# basic_board.net
KiCad netlist of a schematic drawn in EAGLE
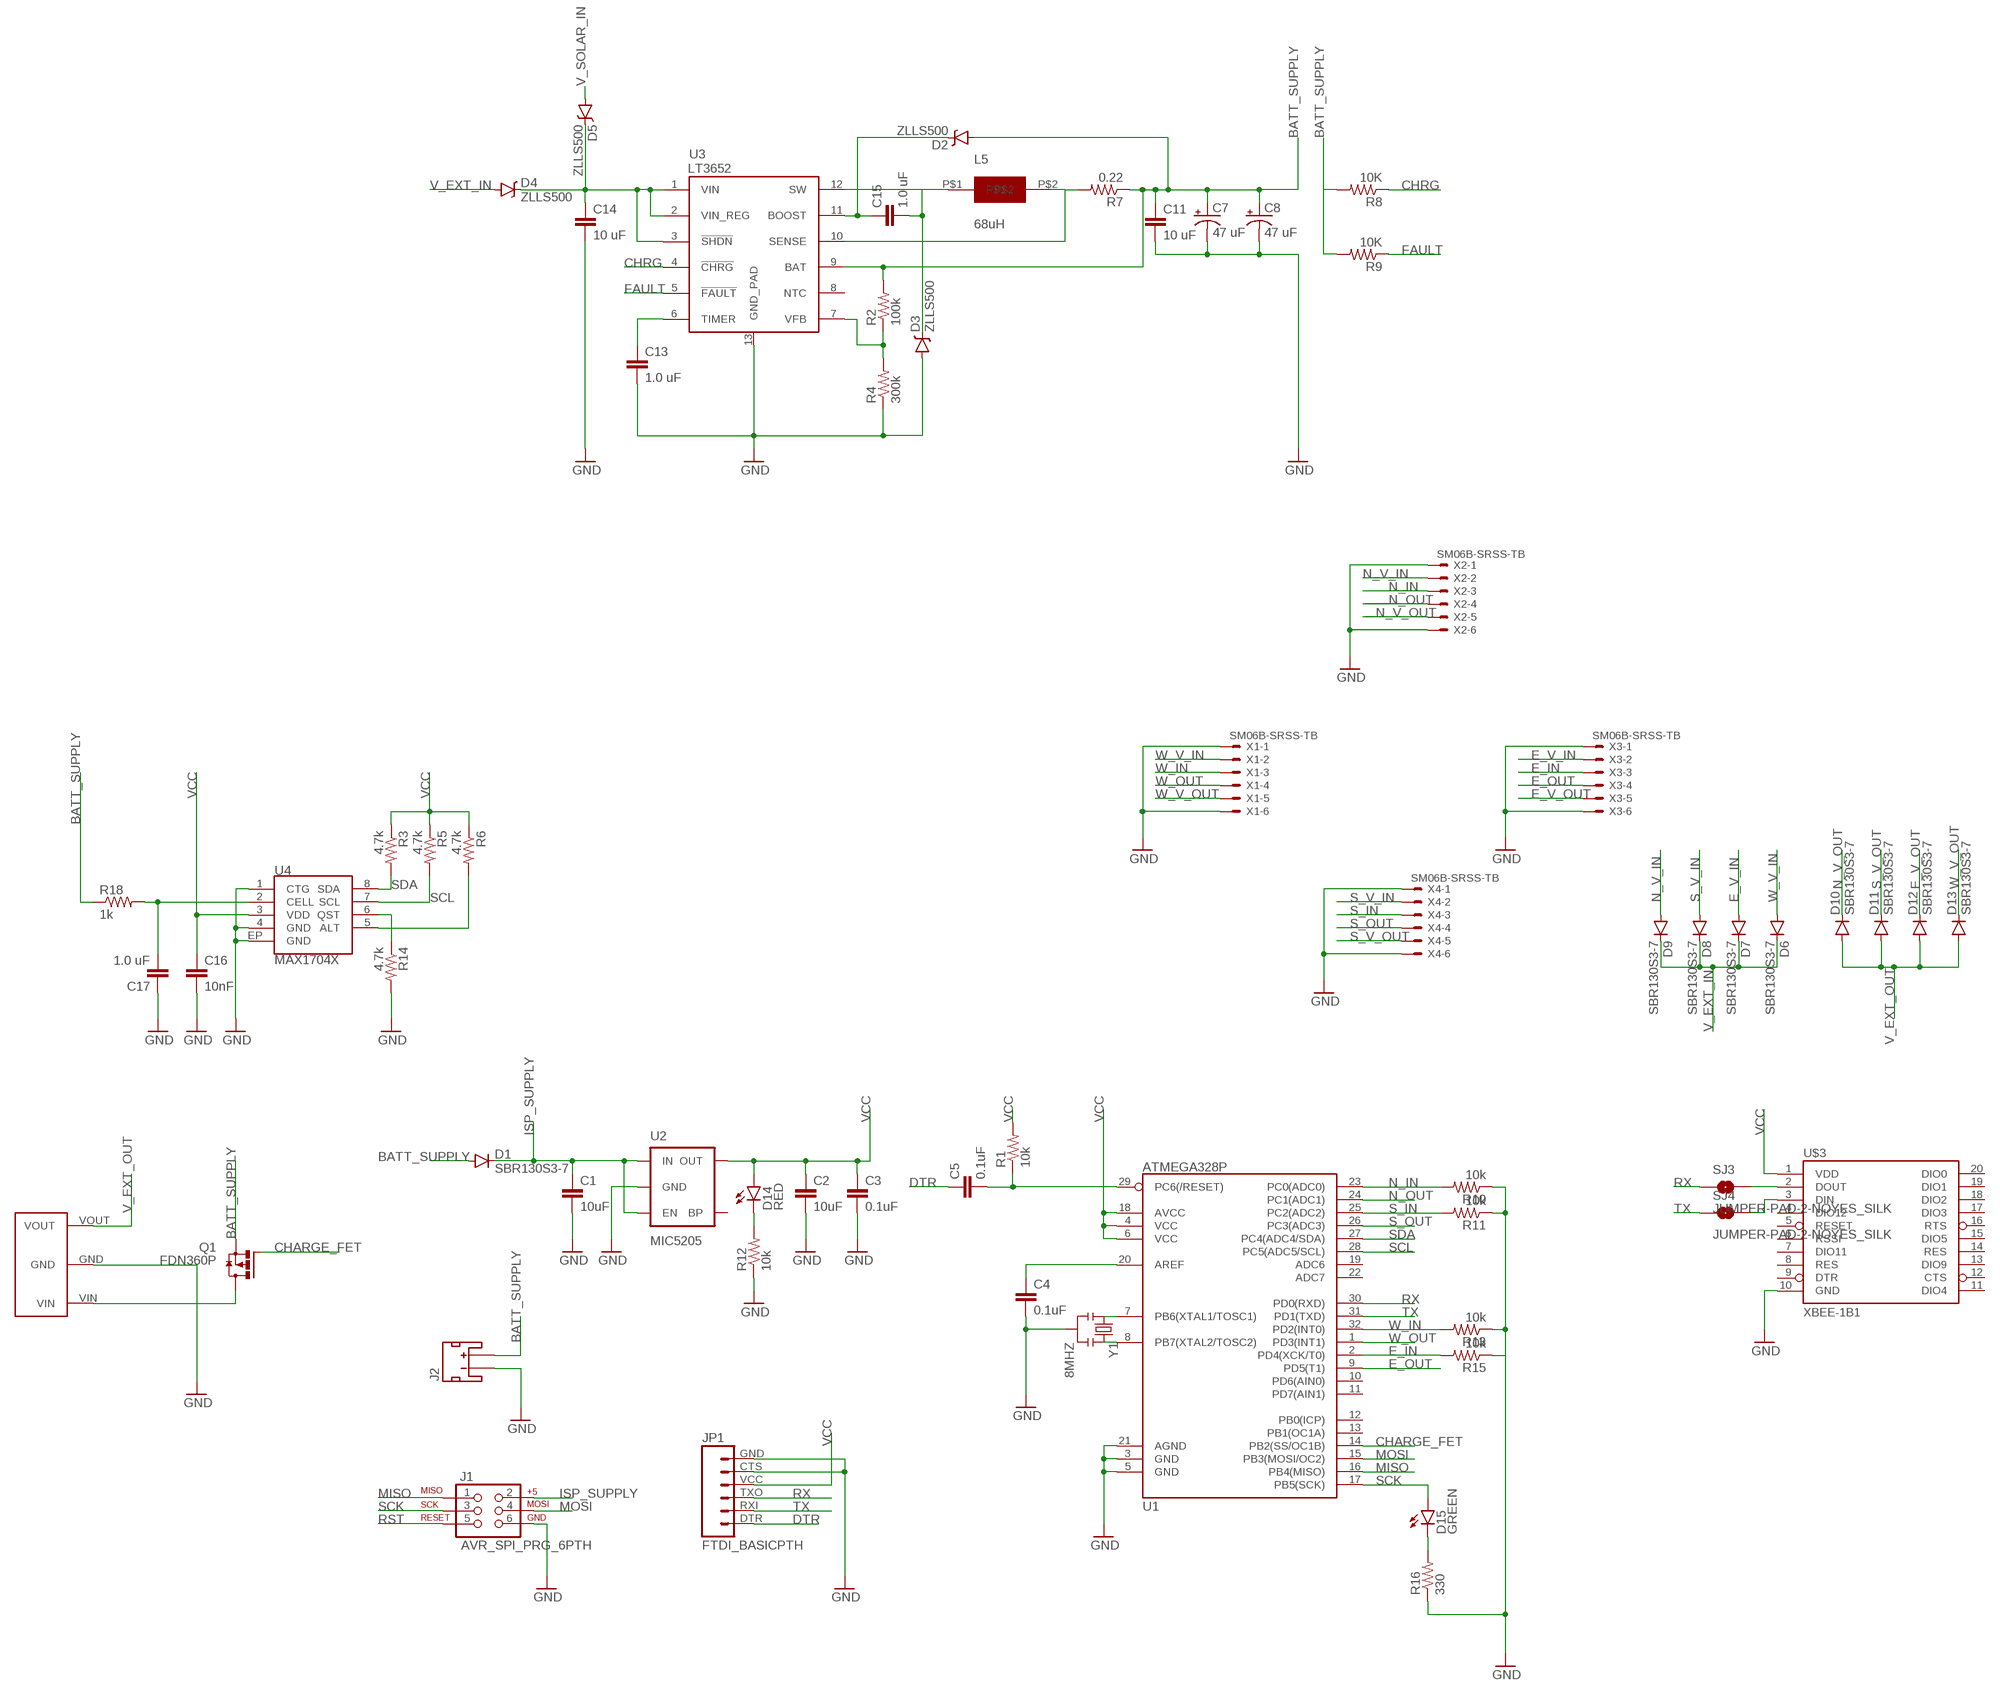
[diagram p0: schematic, sheet 1]

(export (version "E")
  (design (tool "Eeschema 10.0.6"))
  (components
    (comp (ref "C1")
      (value "10uF")
      (footprint "eagle-import:1206")
      (libsource (lib "eagle-import") (part "CAP1206"))
    )
    (comp (ref "C2")
      (value "10uF")
      (footprint "eagle-import:1206")
      (libsource (lib "eagle-import") (part "CAP1206"))
    )
    (comp (ref "C3")
      (value "0.1uF")
      (footprint "eagle-import:1206")
      (libsource (lib "eagle-import") (part "CAP1206"))
    )
    (comp (ref "C4")
      (value "0.1uF")
      (footprint "eagle-import:0603-CAP")
      (libsource (lib "eagle-import") (part "SparkFun-Passives_CAP0603-CAP"))
    )
    (comp (ref "C5")
      (value "0.1uF")
      (footprint "eagle-import:0603-CAP")
      (libsource (lib "eagle-import") (part "SparkFun-Passives_CAP0603-CAP"))
    )
    (comp (ref "C7")
      (value "47 uF")
      (footprint "eagle-import:EIA3216")
      (libsource (lib "eagle-import") (part "CAP_POL1206"))
    )
    (comp (ref "C8")
      (value "47 uF")
      (footprint "eagle-import:EIA3216")
      (libsource (lib "eagle-import") (part "CAP_POL1206"))
    )
    (comp (ref "C11")
      (value "10 uF")
      (footprint "eagle-import:1206")
      (libsource (lib "eagle-import") (part "10UF-6.3V-20%(1206)"))
    )
    (comp (ref "C13")
      (value "1.0 uF")
      (footprint "eagle-import:1206")
      (libsource (lib "eagle-import") (part "10UF-6.3V-20%(1206)"))
    )
    (comp (ref "C14")
      (value "10 uF")
      (footprint "eagle-import:1206")
      (libsource (lib "eagle-import") (part "10UF-6.3V-20%(1206)"))
    )
    (comp (ref "C15")
      (value "1.0 uF")
      (footprint "eagle-import:1206")
      (libsource (lib "eagle-import") (part "10UF-6.3V-20%(1206)"))
    )
    (comp (ref "C16")
      (value "10nF")
      (footprint "eagle-import:0603-CAP")
      (libsource (lib "eagle-import") (part "SparkFun-Passives_CAP0603-CAP"))
    )
    (comp (ref "C17")
      (value "1.0 uF")
      (footprint "eagle-import:0603-CAP")
      (libsource (lib "eagle-import") (part "SparkFun-Passives_CAP0603-CAP"))
    )
    (comp (ref "D1")
      (value "SBR130S3-7")
      (footprint "eagle-import:SOD-323")
      (libsource (lib "eagle-import") (part "DIODESOD"))
    )
    (comp (ref "D2")
      (value "ZLLS500")
      (footprint "eagle-import:SOT23")
      (libsource (lib "eagle-import") (part "ZLLS500ZLLS500"))
    )
    (comp (ref "D3")
      (value "ZLLS500")
      (footprint "eagle-import:SOT23")
      (libsource (lib "eagle-import") (part "ZLLS500ZLLS500"))
    )
    (comp (ref "D4")
      (value "ZLLS500")
      (footprint "eagle-import:SOT23")
      (libsource (lib "eagle-import") (part "ZLLS500ZLLS500"))
    )
    (comp (ref "D5")
      (value "ZLLS500")
      (footprint "eagle-import:SOT23")
      (libsource (lib "eagle-import") (part "ZLLS500ZLLS500"))
    )
    (comp (ref "D6")
      (value "SBR130S3-7")
      (footprint "eagle-import:SOD-323")
      (libsource (lib "eagle-import") (part "DIODESOD"))
    )
    (comp (ref "D7")
      (value "SBR130S3-7")
      (footprint "eagle-import:SOD-323")
      (libsource (lib "eagle-import") (part "DIODESOD"))
    )
    (comp (ref "D8")
      (value "SBR130S3-7")
      (footprint "eagle-import:SOD-323")
      (libsource (lib "eagle-import") (part "DIODESOD"))
    )
    (comp (ref "D9")
      (value "SBR130S3-7")
      (footprint "eagle-import:SOD-323")
      (libsource (lib "eagle-import") (part "DIODESOD"))
    )
    (comp (ref "D10")
      (value "SBR130S3-7")
      (footprint "eagle-import:SOD-323")
      (libsource (lib "eagle-import") (part "DIODESOD"))
    )
    (comp (ref "D11")
      (value "SBR130S3-7")
      (footprint "eagle-import:SOD-323")
      (libsource (lib "eagle-import") (part "DIODESOD"))
    )
    (comp (ref "D12")
      (value "SBR130S3-7")
      (footprint "eagle-import:SOD-323")
      (libsource (lib "eagle-import") (part "DIODESOD"))
    )
    (comp (ref "D13")
      (value "SBR130S3-7")
      (footprint "eagle-import:SOD-323")
      (libsource (lib "eagle-import") (part "DIODESOD"))
    )
    (comp (ref "D14")
      (value "RED")
      (footprint "eagle-import:LED-0603")
      (libsource (lib "eagle-import") (part "LED-RED0603"))
    )
    (comp (ref "D15")
      (value "GREEN")
      (footprint "eagle-import:LED-0603")
      (libsource (lib "eagle-import") (part "LED-GREEN0603"))
    )
    (comp (ref "J1")
      (value "AVR_SPI_PRG_6PTH")
      (footprint "eagle-import:2X3")
      (libsource (lib "eagle-import") (part "AVR_SPI_PRG_6PTH"))
    )
    (comp (ref "J2")
      (value "JST_2MM_MALE")
      (footprint "eagle-import:JST-2-SMD")
      (libsource (lib "eagle-import") (part "JST_2MM_MALE"))
    )
    (comp (ref "JP1")
      (value "FTDI_BASICPTH")
      (footprint "eagle-import:FTDI_BASIC")
      (libsource (lib "eagle-import") (part "FTDI_BASICPTH"))
    )
    (comp (ref "L5")
      (value "68uH")
      (footprint "eagle-import:MURATA_29L68C")
      (libsource (lib "eagle-import") (part "MURATA_29L683CSMD1"))
    )
    (comp (ref "Q1")
      (value "FDN360P")
      (footprint "eagle-import:SUPER-SOT3")
      (libsource (lib "eagle-import") (part "FDN360P"))
    )
    (comp (ref "R1")
      (value "10k")
      (footprint "eagle-import:0603-RES")
      (libsource (lib "eagle-import") (part "RESISTOR0603-RES"))
    )
    (comp (ref "R2")
      (value "100k")
      (footprint "eagle-import:1206")
      (libsource (lib "eagle-import") (part "SparkFun-Resistors_RESISTOR1206"))
    )
    (comp (ref "R3")
      (value "4.7k")
      (footprint "eagle-import:0603-RES")
      (libsource (lib "eagle-import") (part "RESISTOR0603-RES"))
    )
    (comp (ref "R4")
      (value "300k")
      (footprint "eagle-import:1206")
      (libsource (lib "eagle-import") (part "SparkFun-Resistors_RESISTOR1206"))
    )
    (comp (ref "R5")
      (value "4.7k")
      (footprint "eagle-import:0603-RES")
      (libsource (lib "eagle-import") (part "RESISTOR0603-RES"))
    )
    (comp (ref "R6")
      (value "4.7k")
      (footprint "eagle-import:0603-RES")
      (libsource (lib "eagle-import") (part "RESISTOR0603-RES"))
    )
    (comp (ref "R7")
      (value "0.22")
      (footprint "eagle-import:1206")
      (libsource (lib "eagle-import") (part "SparkFun-Resistors_RESISTOR1206"))
    )
    (comp (ref "R8")
      (value "10K")
      (footprint "eagle-import:1206")
      (libsource (lib "eagle-import") (part "SparkFun-Resistors_RESISTOR1206"))
    )
    (comp (ref "R9")
      (value "10K")
      (footprint "eagle-import:1206")
      (libsource (lib "eagle-import") (part "SparkFun-Resistors_RESISTOR1206"))
    )
    (comp (ref "R10")
      (value "10k")
      (footprint "eagle-import:0603-RES")
      (libsource (lib "eagle-import") (part "RESISTOR0603-RES"))
    )
    (comp (ref "R11")
      (value "10k")
      (footprint "eagle-import:0603-RES")
      (libsource (lib "eagle-import") (part "RESISTOR0603-RES"))
    )
    (comp (ref "R12")
      (value "10k")
      (footprint "eagle-import:1206")
      (libsource (lib "eagle-import") (part "SparkFun-Resistors_RESISTOR1206"))
    )
    (comp (ref "R13")
      (value "10k")
      (footprint "eagle-import:0603-RES")
      (libsource (lib "eagle-import") (part "RESISTOR0603-RES"))
    )
    (comp (ref "R14")
      (value "4.7k")
      (footprint "eagle-import:0603-RES")
      (libsource (lib "eagle-import") (part "RESISTOR0603-RES"))
    )
    (comp (ref "R15")
      (value "10k")
      (footprint "eagle-import:0603-RES")
      (libsource (lib "eagle-import") (part "RESISTOR0603-RES"))
    )
    (comp (ref "R16")
      (value "330")
      (footprint "eagle-import:1206")
      (libsource (lib "eagle-import") (part "SparkFun-Resistors_RESISTOR1206"))
    )
    (comp (ref "R18")
      (value "1k")
      (footprint "eagle-import:0603-RES")
      (libsource (lib "eagle-import") (part "RESISTOR0603-RES"))
    )
    (comp (ref "SJ3")
      (value "JUMPER-PAD-2-NOYES_SILK")
      (footprint "eagle-import:PAD-JUMPER-2-NO_YES_SILK")
      (libsource (lib "eagle-import") (part "JUMPER-PAD-2-NOYES_SILK"))
    )
    (comp (ref "SJ4")
      (value "JUMPER-PAD-2-NOYES_SILK")
      (footprint "eagle-import:PAD-JUMPER-2-NO_YES_SILK")
      (libsource (lib "eagle-import") (part "JUMPER-PAD-2-NOYES_SILK"))
    )
    (comp (ref "U$1")
      (value "POLOLU791BOOSTPOLOLU")
      (footprint "eagle-import:POLOLU791_BOOST")
      (libsource (lib "eagle-import") (part "POLOLU791BOOSTPOLOLU"))
    )
    (comp (ref "U$3")
      (value "XBEE-1B1")
      (footprint "eagle-import:XBEE-1")
      (libsource (lib "eagle-import") (part "XBEE-1B1"))
    )
    (comp (ref "U1")
      (value "ATMEGA328P")
      (footprint "eagle-import:TQFP32-08")
      (libsource (lib "eagle-import") (part "ATMEGA328_SMT"))
    )
    (comp (ref "U2")
      (value "MIC5205")
      (footprint "eagle-import:SOT23-5")
      (libsource (lib "eagle-import") (part "MIC52053.3V"))
    )
    (comp (ref "U3")
      (value "LT3652")
      (footprint "eagle-import:MSOP-12_GND")
      (libsource (lib "eagle-import") (part "LT3652"))
    )
    (comp (ref "U4")
      (value "MAX1704X")
      (footprint "eagle-import:TDFN-8")
      (libsource (lib "eagle-import") (part "MAX1704X"))
    )
    (comp (ref "X1")
      (value "SM06B-SRSS-TB")
      (footprint "eagle-import:SM06B-SRSS-TB")
      (libsource (lib "eagle-import") (part "?M06B-SRSS-TBS"))
    )
    (comp (ref "X2")
      (value "SM06B-SRSS-TB")
      (footprint "eagle-import:SM06B-SRSS-TB")
      (libsource (lib "eagle-import") (part "?M06B-SRSS-TBS"))
    )
    (comp (ref "X3")
      (value "SM06B-SRSS-TB")
      (footprint "eagle-import:SM06B-SRSS-TB")
      (libsource (lib "eagle-import") (part "?M06B-SRSS-TBS"))
    )
    (comp (ref "X4")
      (value "SM06B-SRSS-TB")
      (footprint "eagle-import:SM06B-SRSS-TB")
      (libsource (lib "eagle-import") (part "?M06B-SRSS-TBS"))
    )
    (comp (ref "Y1")
      (value "8MHZ")
      (footprint "eagle-import:RESONATOR-SMD")
      (libsource (lib "eagle-import") (part "RESONATOR8MHZ"))
    )
  )
  (nets
    (net (code "1") (name "/BATT_SUPPLY") (class "Default")
      (node (ref "C11") (pin "1") (pinfunction "1_1") (pintype "passive"))
      (node (ref "C7") (pin "A") (pinfunction "+_A") (pintype "passive"))
      (node (ref "C8") (pin "A") (pinfunction "+_A") (pintype "passive"))
      (node (ref "D1") (pin "A") (pinfunction "A_A") (pintype "passive"))
      (node (ref "D2") (pin "1") (pinfunction "A_1") (pintype "passive"))
      (node (ref "J2") (pin "2") (pinfunction "+_2") (pintype "bidirectional"))
      (node (ref "Q1") (pin "2") (pinfunction "S_2") (pintype "passive"))
      (node (ref "R18") (pin "1") (pinfunction "1_1") (pintype "passive"))
      (node (ref "R2") (pin "2") (pinfunction "2_2") (pintype "passive"))
      (node (ref "R7") (pin "1") (pinfunction "1_1") (pintype "passive"))
      (node (ref "R8") (pin "2") (pinfunction "2_2") (pintype "passive"))
      (node (ref "R9") (pin "2") (pinfunction "2_2") (pintype "passive"))
      (node (ref "U3") (pin "9") (pinfunction "BAT_9") (pintype "bidirectional"))
    )
    (net (code "2") (name "/CHARGE_FET") (class "Default")
      (node (ref "Q1") (pin "1") (pinfunction "G_1") (pintype "passive"))
      (node (ref "U1") (pin "14") (pinfunction "PB2(SS/OC1B)_14") (pintype "bidirectional"))
    )
    (net (code "3") (name "/CHRG") (class "Default")
      (node (ref "R8") (pin "1") (pinfunction "1_1") (pintype "passive"))
      (node (ref "U3") (pin "4") (pinfunction "~{CHRG}_4") (pintype "bidirectional"))
    )
    (net (code "4") (name "/DTR") (class "Default")
      (node (ref "C5") (pin "1") (pinfunction "1_1") (pintype "passive"))
      (node (ref "JP1") (pin "DTR") (pinfunction "1_DTR") (pintype "passive"))
    )
    (net (code "5") (name "/E_IN") (class "Default")
      (node (ref "R15") (pin "2") (pinfunction "2_2") (pintype "passive"))
      (node (ref "U1") (pin "2") (pinfunction "PD4(XCK/T0)_2") (pintype "bidirectional"))
      (node (ref "X3") (pin "3") (pinfunction "S_3") (pintype "passive"))
    )
    (net (code "6") (name "/E_OUT") (class "Default")
      (node (ref "U1") (pin "9") (pinfunction "PD5(T1)_9") (pintype "bidirectional"))
      (node (ref "X3") (pin "4") (pinfunction "S_4") (pintype "passive"))
    )
    (net (code "7") (name "/E_V_IN") (class "Default")
      (node (ref "D7") (pin "A") (pinfunction "A_A") (pintype "passive"))
      (node (ref "X3") (pin "2") (pinfunction "S_2") (pintype "passive"))
    )
    (net (code "8") (name "/E_V_OUT") (class "Default")
      (node (ref "D12") (pin "C") (pinfunction "C_C") (pintype "passive"))
      (node (ref "X3") (pin "5") (pinfunction "S_5") (pintype "passive"))
    )
    (net (code "9") (name "/FAULT") (class "Default")
      (node (ref "R9") (pin "1") (pinfunction "1_1") (pintype "passive"))
      (node (ref "U3") (pin "5") (pinfunction "~{FAULT}_5") (pintype "bidirectional"))
    )
    (net (code "10") (name "/ISP_SUPPLY") (class "Default")
      (node (ref "C1") (pin "1") (pinfunction "1_1") (pintype "passive"))
      (node (ref "D1") (pin "C") (pinfunction "C_C") (pintype "passive"))
      (node (ref "J1") (pin "2") (pinfunction "2_2") (pintype "passive"))
      (node (ref "U2") (pin "1") (pinfunction "IN_1") (pintype "input"))
      (node (ref "U2") (pin "3") (pinfunction "EN_3") (pintype "input"))
    )
    (net (code "11") (name "/MISO") (class "Default")
      (node (ref "J1") (pin "1") (pinfunction "1_1") (pintype "passive"))
      (node (ref "U1") (pin "16") (pinfunction "PB4(MISO)_16") (pintype "bidirectional"))
    )
    (net (code "12") (name "/MOSI") (class "Default")
      (node (ref "J1") (pin "4") (pinfunction "4_4") (pintype "passive"))
      (node (ref "U1") (pin "15") (pinfunction "PB3(MOSI/OC2)_15") (pintype "bidirectional"))
    )
    (net (code "13") (name "/N_IN") (class "Default")
      (node (ref "R10") (pin "2") (pinfunction "2_2") (pintype "passive"))
      (node (ref "U1") (pin "23") (pinfunction "PC0(ADC0)_23") (pintype "bidirectional"))
      (node (ref "X2") (pin "3") (pinfunction "S_3") (pintype "passive"))
    )
    (net (code "14") (name "/N_OUT") (class "Default")
      (node (ref "U1") (pin "24") (pinfunction "PC1(ADC1)_24") (pintype "bidirectional"))
      (node (ref "X2") (pin "4") (pinfunction "S_4") (pintype "passive"))
    )
    (net (code "15") (name "/N_V_IN") (class "Default")
      (node (ref "D9") (pin "A") (pinfunction "A_A") (pintype "passive"))
      (node (ref "X2") (pin "2") (pinfunction "S_2") (pintype "passive"))
    )
    (net (code "16") (name "/N_V_OUT") (class "Default")
      (node (ref "D10") (pin "C") (pinfunction "C_C") (pintype "passive"))
      (node (ref "X2") (pin "5") (pinfunction "S_5") (pintype "passive"))
    )
    (net (code "17") (name "/RST") (class "Default")
      (node (ref "C5") (pin "2") (pinfunction "2_2") (pintype "passive"))
      (node (ref "J1") (pin "5") (pinfunction "5_5") (pintype "passive"))
      (node (ref "R1") (pin "1") (pinfunction "1_1") (pintype "passive"))
      (node (ref "U1") (pin "29") (pinfunction "PC6(/RESET)_29") (pintype "bidirectional"))
    )
    (net (code "18") (name "/RX") (class "Default")
      (node (ref "JP1") (pin "TXO") (pinfunction "3_TXO") (pintype "passive"))
      (node (ref "SJ3") (pin "1") (pinfunction "1_1") (pintype "passive"))
      (node (ref "U1") (pin "30") (pinfunction "PD0(RXD)_30") (pintype "bidirectional"))
    )
    (net (code "19") (name "/SCK") (class "Default")
      (node (ref "D15") (pin "A") (pinfunction "A_A") (pintype "passive"))
      (node (ref "J1") (pin "3") (pinfunction "3_3") (pintype "passive"))
      (node (ref "U1") (pin "17") (pinfunction "PB5(SCK)_17") (pintype "bidirectional"))
    )
    (net (code "20") (name "/SCL") (class "Default")
      (node (ref "R5") (pin "2") (pinfunction "2_2") (pintype "passive"))
      (node (ref "U1") (pin "28") (pinfunction "PC5(ADC5/SCL)_28") (pintype "bidirectional"))
      (node (ref "U4") (pin "7") (pinfunction "SCL_7") (pintype "bidirectional"))
    )
    (net (code "21") (name "/SDA") (class "Default")
      (node (ref "R3") (pin "2") (pinfunction "2_2") (pintype "passive"))
      (node (ref "U1") (pin "27") (pinfunction "PC4(ADC4/SDA)_27") (pintype "bidirectional"))
      (node (ref "U4") (pin "8") (pinfunction "SDA_8") (pintype "bidirectional"))
    )
    (net (code "22") (name "/S_IN") (class "Default")
      (node (ref "R11") (pin "2") (pinfunction "2_2") (pintype "passive"))
      (node (ref "U1") (pin "25") (pinfunction "PC2(ADC2)_25") (pintype "bidirectional"))
      (node (ref "X4") (pin "3") (pinfunction "S_3") (pintype "passive"))
    )
    (net (code "23") (name "/S_OUT") (class "Default")
      (node (ref "U1") (pin "26") (pinfunction "PC3(ADC3)_26") (pintype "bidirectional"))
      (node (ref "X4") (pin "4") (pinfunction "S_4") (pintype "passive"))
    )
    (net (code "24") (name "/S_V_IN") (class "Default")
      (node (ref "D8") (pin "A") (pinfunction "A_A") (pintype "passive"))
      (node (ref "X4") (pin "2") (pinfunction "S_2") (pintype "passive"))
    )
    (net (code "25") (name "/S_V_OUT") (class "Default")
      (node (ref "D11") (pin "C") (pinfunction "C_C") (pintype "passive"))
      (node (ref "X4") (pin "5") (pinfunction "S_5") (pintype "passive"))
    )
    (net (code "26") (name "/TX") (class "Default")
      (node (ref "JP1") (pin "RXI") (pinfunction "2_RXI") (pintype "passive"))
      (node (ref "SJ4") (pin "1") (pinfunction "1_1") (pintype "passive"))
      (node (ref "U1") (pin "31") (pinfunction "PD1(TXD)_31") (pintype "bidirectional"))
    )
    (net (code "27") (name "/VCC") (class "Default")
      (node (ref "C16") (pin "1") (pinfunction "1_1") (pintype "passive"))
      (node (ref "C2") (pin "1") (pinfunction "1_1") (pintype "passive"))
      (node (ref "C3") (pin "1") (pinfunction "1_1") (pintype "passive"))
      (node (ref "D14") (pin "A") (pinfunction "A_A") (pintype "passive"))
      (node (ref "JP1") (pin "VCC") (pinfunction "4_VCC") (pintype "passive"))
      (node (ref "R1") (pin "2") (pinfunction "2_2") (pintype "passive"))
      (node (ref "R3") (pin "1") (pinfunction "1_1") (pintype "passive"))
      (node (ref "R5") (pin "1") (pinfunction "1_1") (pintype "passive"))
      (node (ref "R6") (pin "1") (pinfunction "1_1") (pintype "passive"))
      (node (ref "U$3") (pin "1") (pinfunction "VDD_1") (pintype "power_in"))
      (node (ref "U1") (pin "18") (pinfunction "AVCC_18") (pintype "bidirectional"))
      (node (ref "U1") (pin "4") (pinfunction "VCC_4") (pintype "bidirectional"))
      (node (ref "U1") (pin "6") (pinfunction "VCC_6") (pintype "bidirectional"))
      (node (ref "U2") (pin "5") (pinfunction "OUT_5") (pintype "passive"))
      (node (ref "U4") (pin "3") (pinfunction "VDD_3") (pintype "bidirectional"))
    )
    (net (code "28") (name "/V_EXT_IN") (class "Default")
      (node (ref "D4") (pin "1") (pinfunction "A_1") (pintype "passive"))
      (node (ref "D6") (pin "C") (pinfunction "C_C") (pintype "passive"))
      (node (ref "D7") (pin "C") (pinfunction "C_C") (pintype "passive"))
      (node (ref "D8") (pin "C") (pinfunction "C_C") (pintype "passive"))
      (node (ref "D9") (pin "C") (pinfunction "C_C") (pintype "passive"))
    )
    (net (code "29") (name "/V_EXT_OUT") (class "Default")
      (node (ref "D10") (pin "A") (pinfunction "A_A") (pintype "passive"))
      (node (ref "D11") (pin "A") (pinfunction "A_A") (pintype "passive"))
      (node (ref "D12") (pin "A") (pinfunction "A_A") (pintype "passive"))
      (node (ref "D13") (pin "A") (pinfunction "A_A") (pintype "passive"))
      (node (ref "U$1") (pin "VOUT") (pinfunction "VOUT_VOUT") (pintype "bidirectional"))
    )
    (net (code "30") (name "/V_SOLAR_IN") (class "Default")
      (node (ref "D5") (pin "1") (pinfunction "A_1") (pintype "passive"))
    )
    (net (code "31") (name "/W_IN") (class "Default")
      (node (ref "R13") (pin "2") (pinfunction "2_2") (pintype "passive"))
      (node (ref "U1") (pin "32") (pinfunction "PD2(INT0)_32") (pintype "bidirectional"))
      (node (ref "X1") (pin "3") (pinfunction "S_3") (pintype "passive"))
    )
    (net (code "32") (name "/W_OUT") (class "Default")
      (node (ref "U1") (pin "1") (pinfunction "PD3(INT1)_1") (pintype "bidirectional"))
      (node (ref "X1") (pin "4") (pinfunction "S_4") (pintype "passive"))
    )
    (net (code "33") (name "/W_V_IN") (class "Default")
      (node (ref "D6") (pin "A") (pinfunction "A_A") (pintype "passive"))
      (node (ref "X1") (pin "2") (pinfunction "S_2") (pintype "passive"))
    )
    (net (code "34") (name "/W_V_OUT") (class "Default")
      (node (ref "D13") (pin "C") (pinfunction "C_C") (pintype "passive"))
      (node (ref "X1") (pin "5") (pinfunction "S_5") (pintype "passive"))
    )
    (net (code "35") (name "GND") (class "Default")
      (node (ref "C1") (pin "2") (pinfunction "2_2") (pintype "passive"))
      (node (ref "C11") (pin "2") (pinfunction "2_2") (pintype "passive"))
      (node (ref "C13") (pin "2") (pinfunction "2_2") (pintype "passive"))
      (node (ref "C14") (pin "2") (pinfunction "2_2") (pintype "passive"))
      (node (ref "C16") (pin "2") (pinfunction "2_2") (pintype "passive"))
      (node (ref "C17") (pin "1") (pinfunction "1_1") (pintype "passive"))
      (node (ref "C2") (pin "2") (pinfunction "2_2") (pintype "passive"))
      (node (ref "C3") (pin "2") (pinfunction "2_2") (pintype "passive"))
      (node (ref "C4") (pin "2") (pinfunction "2_2") (pintype "passive"))
      (node (ref "C7") (pin "C") (pinfunction "-_C") (pintype "passive"))
      (node (ref "C8") (pin "C") (pinfunction "-_C") (pintype "passive"))
      (node (ref "D3") (pin "1") (pinfunction "A_1") (pintype "passive"))
      (node (ref "J1") (pin "6") (pinfunction "6_6") (pintype "passive"))
      (node (ref "J2") (pin "1") (pinfunction "-_1") (pintype "bidirectional"))
      (node (ref "JP1") (pin "CTS") (pinfunction "5_CTS") (pintype "passive"))
      (node (ref "JP1") (pin "GND") (pinfunction "6_GND") (pintype "passive"))
      (node (ref "R10") (pin "1") (pinfunction "1_1") (pintype "passive"))
      (node (ref "R11") (pin "1") (pinfunction "1_1") (pintype "passive"))
      (node (ref "R12") (pin "1") (pinfunction "1_1") (pintype "passive"))
      (node (ref "R13") (pin "1") (pinfunction "1_1") (pintype "passive"))
      (node (ref "R14") (pin "2") (pinfunction "2_2") (pintype "passive"))
      (node (ref "R15") (pin "1") (pinfunction "1_1") (pintype "passive"))
      (node (ref "R16") (pin "1") (pinfunction "1_1") (pintype "passive"))
      (node (ref "R4") (pin "1") (pinfunction "1_1") (pintype "passive"))
      (node (ref "U$1") (pin "GND") (pinfunction "GND_GND") (pintype "bidirectional"))
      (node (ref "U$3") (pin "10") (pinfunction "GND_10") (pintype "power_in"))
      (node (ref "U1") (pin "21") (pinfunction "AGND_21") (pintype "bidirectional"))
      (node (ref "U1") (pin "3") (pinfunction "GND_3") (pintype "bidirectional"))
      (node (ref "U1") (pin "5") (pinfunction "GND_5") (pintype "bidirectional"))
      (node (ref "U2") (pin "2") (pinfunction "GND_2") (pintype "input"))
      (node (ref "U3") (pin "13") (pinfunction "GND_PAD_13") (pintype "bidirectional"))
      (node (ref "U4") (pin "1") (pinfunction "CTG_1") (pintype "bidirectional"))
      (node (ref "U4") (pin "4") (pinfunction "GND_4") (pintype "bidirectional"))
      (node (ref "U4") (pin "EP") (pinfunction "GND_EP") (pintype "bidirectional"))
      (node (ref "X1") (pin "1") (pinfunction "S_1") (pintype "passive"))
      (node (ref "X1") (pin "6") (pinfunction "S_6") (pintype "passive"))
      (node (ref "X2") (pin "1") (pinfunction "S_1") (pintype "passive"))
      (node (ref "X2") (pin "6") (pinfunction "S_6") (pintype "passive"))
      (node (ref "X3") (pin "1") (pinfunction "S_1") (pintype "passive"))
      (node (ref "X3") (pin "6") (pinfunction "S_6") (pintype "passive"))
      (node (ref "X4") (pin "1") (pinfunction "S_1") (pintype "passive"))
      (node (ref "X4") (pin "6") (pinfunction "S_6") (pintype "passive"))
      (node (ref "Y1") (pin "2") (pinfunction "2_2") (pintype "passive"))
    )
    (net (code "36") (name "Net-(D2-C)") (class "Default")
      (node (ref "C15") (pin "1") (pinfunction "1_1") (pintype "passive"))
      (node (ref "D2") (pin "3") (pinfunction "C_3") (pintype "passive"))
      (node (ref "U3") (pin "11") (pinfunction "BOOST_11") (pintype "bidirectional"))
    )
    (net (code "37") (name "Net-(D3-C)") (class "Default")
      (node (ref "C15") (pin "2") (pinfunction "2_2") (pintype "passive"))
      (node (ref "D3") (pin "3") (pinfunction "C_3") (pintype "passive"))
      (node (ref "L5") (pin "P$1") (pinfunction "P$1_P$1") (pintype "bidirectional"))
      (node (ref "U3") (pin "12") (pinfunction "SW_12") (pintype "bidirectional"))
    )
    (net (code "38") (name "Net-(D4-C)") (class "Default")
      (node (ref "C14") (pin "1") (pinfunction "1_1") (pintype "passive"))
      (node (ref "D4") (pin "3") (pinfunction "C_3") (pintype "passive"))
      (node (ref "D5") (pin "3") (pinfunction "C_3") (pintype "passive"))
      (node (ref "U3") (pin "1") (pinfunction "VIN_1") (pintype "bidirectional"))
      (node (ref "U3") (pin "2") (pinfunction "VIN_REG_2") (pintype "bidirectional"))
      (node (ref "U3") (pin "3") (pinfunction "~{SHDN}_3") (pintype "bidirectional"))
    )
    (net (code "39") (name "Net-(D14-PadC)") (class "Default")
      (node (ref "D14") (pin "C") (pinfunction "C_C") (pintype "passive"))
      (node (ref "R12") (pin "2") (pinfunction "2_2") (pintype "passive"))
    )
    (net (code "40") (name "Net-(D15-PadC)") (class "Default")
      (node (ref "D15") (pin "C") (pinfunction "C_C") (pintype "passive"))
      (node (ref "R16") (pin "2") (pinfunction "2_2") (pintype "passive"))
    )
    (net (code "41") (name "Net-(Q1-D)") (class "Default")
      (node (ref "Q1") (pin "3") (pinfunction "D_3") (pintype "passive"))
      (node (ref "U$1") (pin "VIN") (pinfunction "VIN_VIN") (pintype "bidirectional"))
    )
    (net (code "42") (name "Net-(U$3-DIN)") (class "Default")
      (node (ref "SJ4") (pin "2") (pinfunction "2_2") (pintype "passive"))
      (node (ref "U$3") (pin "3") (pinfunction "DIN_3") (pintype "input"))
    )
    (net (code "43") (name "Net-(U$3-DOUT)") (class "Default")
      (node (ref "SJ3") (pin "2") (pinfunction "2_2") (pintype "passive"))
      (node (ref "U$3") (pin "2") (pinfunction "DOUT_2") (pintype "output"))
    )
    (net (code "44") (name "Net-(U1-AREF)") (class "Default")
      (node (ref "C4") (pin "1") (pinfunction "1_1") (pintype "passive"))
      (node (ref "U1") (pin "20") (pinfunction "AREF_20") (pintype "bidirectional"))
    )
    (net (code "45") (name "Net-(U1-PB6(XTAL1{slash}TOSC1))") (class "Default")
      (node (ref "U1") (pin "7") (pinfunction "PB6(XTAL1/TOSC1)_7") (pintype "bidirectional"))
      (node (ref "Y1") (pin "1") (pinfunction "1_1") (pintype "passive"))
    )
    (net (code "46") (name "Net-(U1-PB7(XTAL2{slash}TOSC2))") (class "Default")
      (node (ref "U1") (pin "8") (pinfunction "PB7(XTAL2/TOSC2)_8") (pintype "bidirectional"))
      (node (ref "Y1") (pin "3") (pinfunction "3_3") (pintype "passive"))
    )
    (net (code "47") (name "Net-(U3-SENSE)") (class "Default")
      (node (ref "L5") (pin "P$2") (pinfunction "P$2_P$2") (pintype "bidirectional"))
      (node (ref "R7") (pin "2") (pinfunction "2_2") (pintype "passive"))
      (node (ref "U3") (pin "10") (pinfunction "SENSE_10") (pintype "bidirectional"))
    )
    (net (code "48") (name "Net-(U3-TIMER)") (class "Default")
      (node (ref "C13") (pin "1") (pinfunction "1_1") (pintype "passive"))
      (node (ref "U3") (pin "6") (pinfunction "TIMER_6") (pintype "bidirectional"))
    )
    (net (code "49") (name "Net-(U3-VFB)") (class "Default")
      (node (ref "R2") (pin "1") (pinfunction "1_1") (pintype "passive"))
      (node (ref "R4") (pin "2") (pinfunction "2_2") (pintype "passive"))
      (node (ref "U3") (pin "7") (pinfunction "VFB_7") (pintype "bidirectional"))
    )
    (net (code "50") (name "Net-(U4-ALT)") (class "Default")
      (node (ref "R6") (pin "2") (pinfunction "2_2") (pintype "passive"))
      (node (ref "U4") (pin "5") (pinfunction "ALT_5") (pintype "bidirectional"))
    )
    (net (code "51") (name "Net-(U4-CELL)") (class "Default")
      (node (ref "C17") (pin "2") (pinfunction "2_2") (pintype "passive"))
      (node (ref "R18") (pin "2") (pinfunction "2_2") (pintype "passive"))
      (node (ref "U4") (pin "2") (pinfunction "CELL_2") (pintype "bidirectional"))
    )
    (net (code "52") (name "Net-(U4-QST)") (class "Default")
      (node (ref "R14") (pin "1") (pinfunction "1_1") (pintype "passive"))
      (node (ref "U4") (pin "6") (pinfunction "QST_6") (pintype "bidirectional"))
    )
    (net (code "53") (name "unconnected-(J2-PAD1-PadNC1)") (class "Default")
      (node (ref "J2") (pin "NC1") (pinfunction "PAD1_NC1") (pintype "bidirectional"))
    )
    (net (code "54") (name "unconnected-(J2-PAD2-PadNC2)") (class "Default")
      (node (ref "J2") (pin "NC2") (pinfunction "PAD2_NC2") (pintype "bidirectional"))
    )
    (net (code "55") (name "unconnected-(U$3-CTS-Pad12)") (class "Default")
      (node (ref "U$3") (pin "12") (pinfunction "CTS_12") (pintype "output"))
    )
    (net (code "56") (name "unconnected-(U$3-DIO0-Pad20)") (class "Default")
      (node (ref "U$3") (pin "20") (pinfunction "DIO0_20") (pintype "bidirectional"))
    )
    (net (code "57") (name "unconnected-(U$3-DIO1-Pad19)") (class "Default")
      (node (ref "U$3") (pin "19") (pinfunction "DIO1_19") (pintype "bidirectional"))
    )
    (net (code "58") (name "unconnected-(U$3-DIO2-Pad18)") (class "Default")
      (node (ref "U$3") (pin "18") (pinfunction "DIO2_18") (pintype "bidirectional"))
    )
    (net (code "59") (name "unconnected-(U$3-DIO3-Pad17)") (class "Default")
      (node (ref "U$3") (pin "17") (pinfunction "DIO3_17") (pintype "bidirectional"))
    )
    (net (code "60") (name "unconnected-(U$3-DIO4-Pad11)") (class "Default")
      (node (ref "U$3") (pin "11") (pinfunction "DIO4_11") (pintype "bidirectional"))
    )
    (net (code "61") (name "unconnected-(U$3-DIO5-Pad15)") (class "Default")
      (node (ref "U$3") (pin "15") (pinfunction "DIO5_15") (pintype "bidirectional"))
    )
    (net (code "62") (name "unconnected-(U$3-DIO9-Pad13)") (class "Default")
      (node (ref "U$3") (pin "13") (pinfunction "DIO9_13") (pintype "bidirectional"))
    )
    (net (code "63") (name "unconnected-(U$3-DIO11-Pad7)") (class "Default")
      (node (ref "U$3") (pin "7") (pinfunction "DIO11_7") (pintype "bidirectional"))
    )
    (net (code "64") (name "unconnected-(U$3-DIO12-Pad4)") (class "Default")
      (node (ref "U$3") (pin "4") (pinfunction "DIO12_4") (pintype "bidirectional"))
    )
    (net (code "65") (name "unconnected-(U$3-DTR-Pad9)") (class "Default")
      (node (ref "U$3") (pin "9") (pinfunction "DTR_9") (pintype "bidirectional"))
    )
    (net (code "66") (name "unconnected-(U$3-RES-Pad8)") (class "Default")
      (node (ref "U$3") (pin "8") (pinfunction "RES_8") (pintype "bidirectional"))
    )
    (net (code "67") (name "unconnected-(U$3-RES-Pad14)") (class "Default")
      (node (ref "U$3") (pin "14") (pinfunction "RES_14") (pintype "bidirectional"))
    )
    (net (code "68") (name "unconnected-(U$3-RESET-Pad5)") (class "Default")
      (node (ref "U$3") (pin "5") (pinfunction "RESET_5") (pintype "input"))
    )
    (net (code "69") (name "unconnected-(U$3-RSSI-Pad6)") (class "Default")
      (node (ref "U$3") (pin "6") (pinfunction "RSSI_6") (pintype "bidirectional"))
    )
    (net (code "70") (name "unconnected-(U$3-RTS-Pad16)") (class "Default")
      (node (ref "U$3") (pin "16") (pinfunction "RTS_16") (pintype "input"))
    )
    (net (code "71") (name "unconnected-(U1-ADC6-Pad19)") (class "Default")
      (node (ref "U1") (pin "19") (pinfunction "ADC6_19") (pintype "bidirectional"))
    )
    (net (code "72") (name "unconnected-(U1-ADC7-Pad22)") (class "Default")
      (node (ref "U1") (pin "22") (pinfunction "ADC7_22") (pintype "bidirectional"))
    )
    (net (code "73") (name "unconnected-(U1-PB0(ICP)-Pad12)") (class "Default")
      (node (ref "U1") (pin "12") (pinfunction "PB0(ICP)_12") (pintype "bidirectional"))
    )
    (net (code "74") (name "unconnected-(U1-PB1(OC1A)-Pad13)") (class "Default")
      (node (ref "U1") (pin "13") (pinfunction "PB1(OC1A)_13") (pintype "bidirectional"))
    )
    (net (code "75") (name "unconnected-(U1-PD6(AIN0)-Pad10)") (class "Default")
      (node (ref "U1") (pin "10") (pinfunction "PD6(AIN0)_10") (pintype "bidirectional"))
    )
    (net (code "76") (name "unconnected-(U1-PD7(AIN1)-Pad11)") (class "Default")
      (node (ref "U1") (pin "11") (pinfunction "PD7(AIN1)_11") (pintype "bidirectional"))
    )
    (net (code "77") (name "unconnected-(U2-BP-Pad4)") (class "Default")
      (node (ref "U2") (pin "4") (pinfunction "BP_4") (pintype "input"))
    )
    (net (code "78") (name "unconnected-(U3-NTC-Pad8)") (class "Default")
      (node (ref "U3") (pin "8") (pinfunction "NTC_8") (pintype "bidirectional"))
    )
  )
)
